# Hydrophones_Array_MMCX_Adapter.net
KiCad netlist of a schematic drawn in Altium Designer
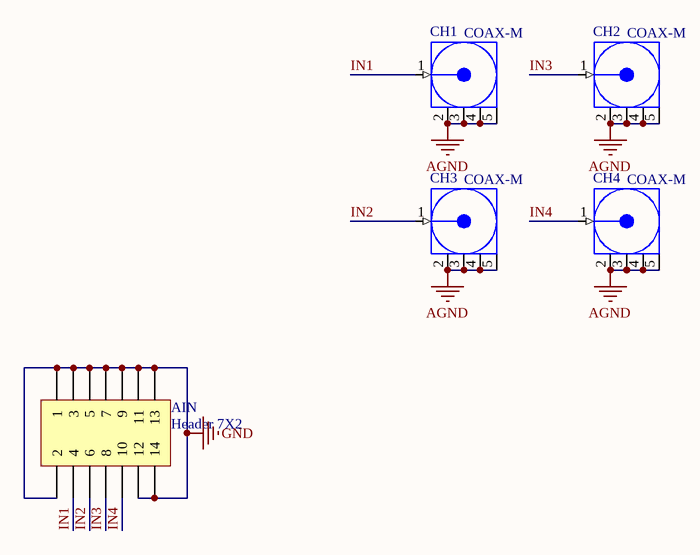
[diagram p0: Hydrophones_Array_MMCX_Adapter.SchDoc]

(export (version "E")
  (design (tool "Eeschema 10.0.6"))
  (components
    (comp (ref "AIN")
      (value "Header 7X2")
      (footprint "FLE-107-01-G-DV-A-TR")
      (description "Header, 7-Pin, Dual row")
      (fields (field (name "PUBLISHER") "Altium Limited"))
      (libsource (lib "Miscellaneous Connectors") (part "Header 7X2"))
    )
    (comp (ref "CH1")
      (value "COAX-M")
      (footprint "MMCX-J-P-H-ST-TH1")
      (description "RF Coaxial PCB Connector, MMCX; Thru-Hole, Vertical Mount Plug,  50 Ohm Impedance")
      (fields (field (name "PUBLISHER") "Altium Limited"))
      (libsource (lib "Miscellaneous Connectors") (part "COAX-M"))
    )
    (comp (ref "CH2")
      (value "COAX-M")
      (footprint "MMCX-J-P-H-ST-TH1")
      (description "RF Coaxial PCB Connector, MMCX; Thru-Hole, Vertical Mount Plug,  50 Ohm Impedance")
      (fields (field (name "PUBLISHER") "Altium Limited"))
      (libsource (lib "Miscellaneous Connectors") (part "COAX-M"))
    )
    (comp (ref "CH3")
      (value "COAX-M")
      (footprint "MMCX-J-P-H-ST-TH1")
      (description "RF Coaxial PCB Connector, MMCX; Thru-Hole, Vertical Mount Plug,  50 Ohm Impedance")
      (fields (field (name "PUBLISHER") "Altium Limited"))
      (libsource (lib "Miscellaneous Connectors") (part "COAX-M"))
    )
    (comp (ref "CH4")
      (value "COAX-M")
      (footprint "MMCX-J-P-H-ST-TH1")
      (description "RF Coaxial PCB Connector, MMCX; Thru-Hole, Vertical Mount Plug,  50 Ohm Impedance")
      (fields (field (name "PUBLISHER") "Altium Limited"))
      (libsource (lib "Miscellaneous Connectors") (part "COAX-M"))
    )
  )
  (nets
    (net (code "1") (name "/IN1") (class "Default")
      (node (ref "AIN") (pin "4") (pinfunction "4_4") (pintype "passive"))
      (node (ref "CH1") (pin "1") (pinfunction "Signal_1") (pintype "input"))
    )
    (net (code "2") (name "/IN2") (class "Default")
      (node (ref "AIN") (pin "6") (pinfunction "6_6") (pintype "passive"))
      (node (ref "CH3") (pin "1") (pinfunction "Signal_1") (pintype "input"))
    )
    (net (code "3") (name "/IN3") (class "Default")
      (node (ref "AIN") (pin "8") (pinfunction "8_8") (pintype "passive"))
      (node (ref "CH2") (pin "1") (pinfunction "Signal_1") (pintype "input"))
    )
    (net (code "4") (name "/IN4") (class "Default")
      (node (ref "AIN") (pin "10") (pinfunction "10_10") (pintype "passive"))
      (node (ref "CH4") (pin "1") (pinfunction "Signal_1") (pintype "input"))
    )
    (net (code "5") (name "AGND") (class "Default")
      (node (ref "CH1") (pin "2") (pinfunction "GND_2") (pintype "power_in"))
      (node (ref "CH1") (pin "3") (pinfunction "GND_3") (pintype "power_in"))
      (node (ref "CH1") (pin "4") (pinfunction "GND_4") (pintype "power_in"))
      (node (ref "CH1") (pin "5") (pinfunction "GND_5") (pintype "power_in"))
      (node (ref "CH2") (pin "2") (pinfunction "GND_2") (pintype "power_in"))
      (node (ref "CH2") (pin "3") (pinfunction "GND_3") (pintype "power_in"))
      (node (ref "CH2") (pin "4") (pinfunction "GND_4") (pintype "power_in"))
      (node (ref "CH2") (pin "5") (pinfunction "GND_5") (pintype "power_in"))
      (node (ref "CH3") (pin "2") (pinfunction "GND_2") (pintype "power_in"))
      (node (ref "CH3") (pin "3") (pinfunction "GND_3") (pintype "power_in"))
      (node (ref "CH3") (pin "4") (pinfunction "GND_4") (pintype "power_in"))
      (node (ref "CH3") (pin "5") (pinfunction "GND_5") (pintype "power_in"))
      (node (ref "CH4") (pin "2") (pinfunction "GND_2") (pintype "power_in"))
      (node (ref "CH4") (pin "3") (pinfunction "GND_3") (pintype "power_in"))
      (node (ref "CH4") (pin "4") (pinfunction "GND_4") (pintype "power_in"))
      (node (ref "CH4") (pin "5") (pinfunction "GND_5") (pintype "power_in"))
    )
    (net (code "6") (name "GND") (class "Default")
      (node (ref "AIN") (pin "1") (pinfunction "1_1") (pintype "passive"))
      (node (ref "AIN") (pin "11") (pinfunction "11_11") (pintype "passive"))
      (node (ref "AIN") (pin "12") (pinfunction "12_12") (pintype "passive"))
      (node (ref "AIN") (pin "13") (pinfunction "13_13") (pintype "passive"))
      (node (ref "AIN") (pin "14") (pinfunction "14_14") (pintype "passive"))
      (node (ref "AIN") (pin "2") (pinfunction "2_2") (pintype "passive"))
      (node (ref "AIN") (pin "3") (pinfunction "3_3") (pintype "passive"))
      (node (ref "AIN") (pin "5") (pinfunction "5_5") (pintype "passive"))
      (node (ref "AIN") (pin "7") (pinfunction "7_7") (pintype "passive"))
      (node (ref "AIN") (pin "9") (pinfunction "9_9") (pintype "passive"))
    )
  )
)
